# LB_BIT_i34_RANDOM-v03_3_4_-OHW.net
KiCad netlist of a schematic drawn in EAGLE
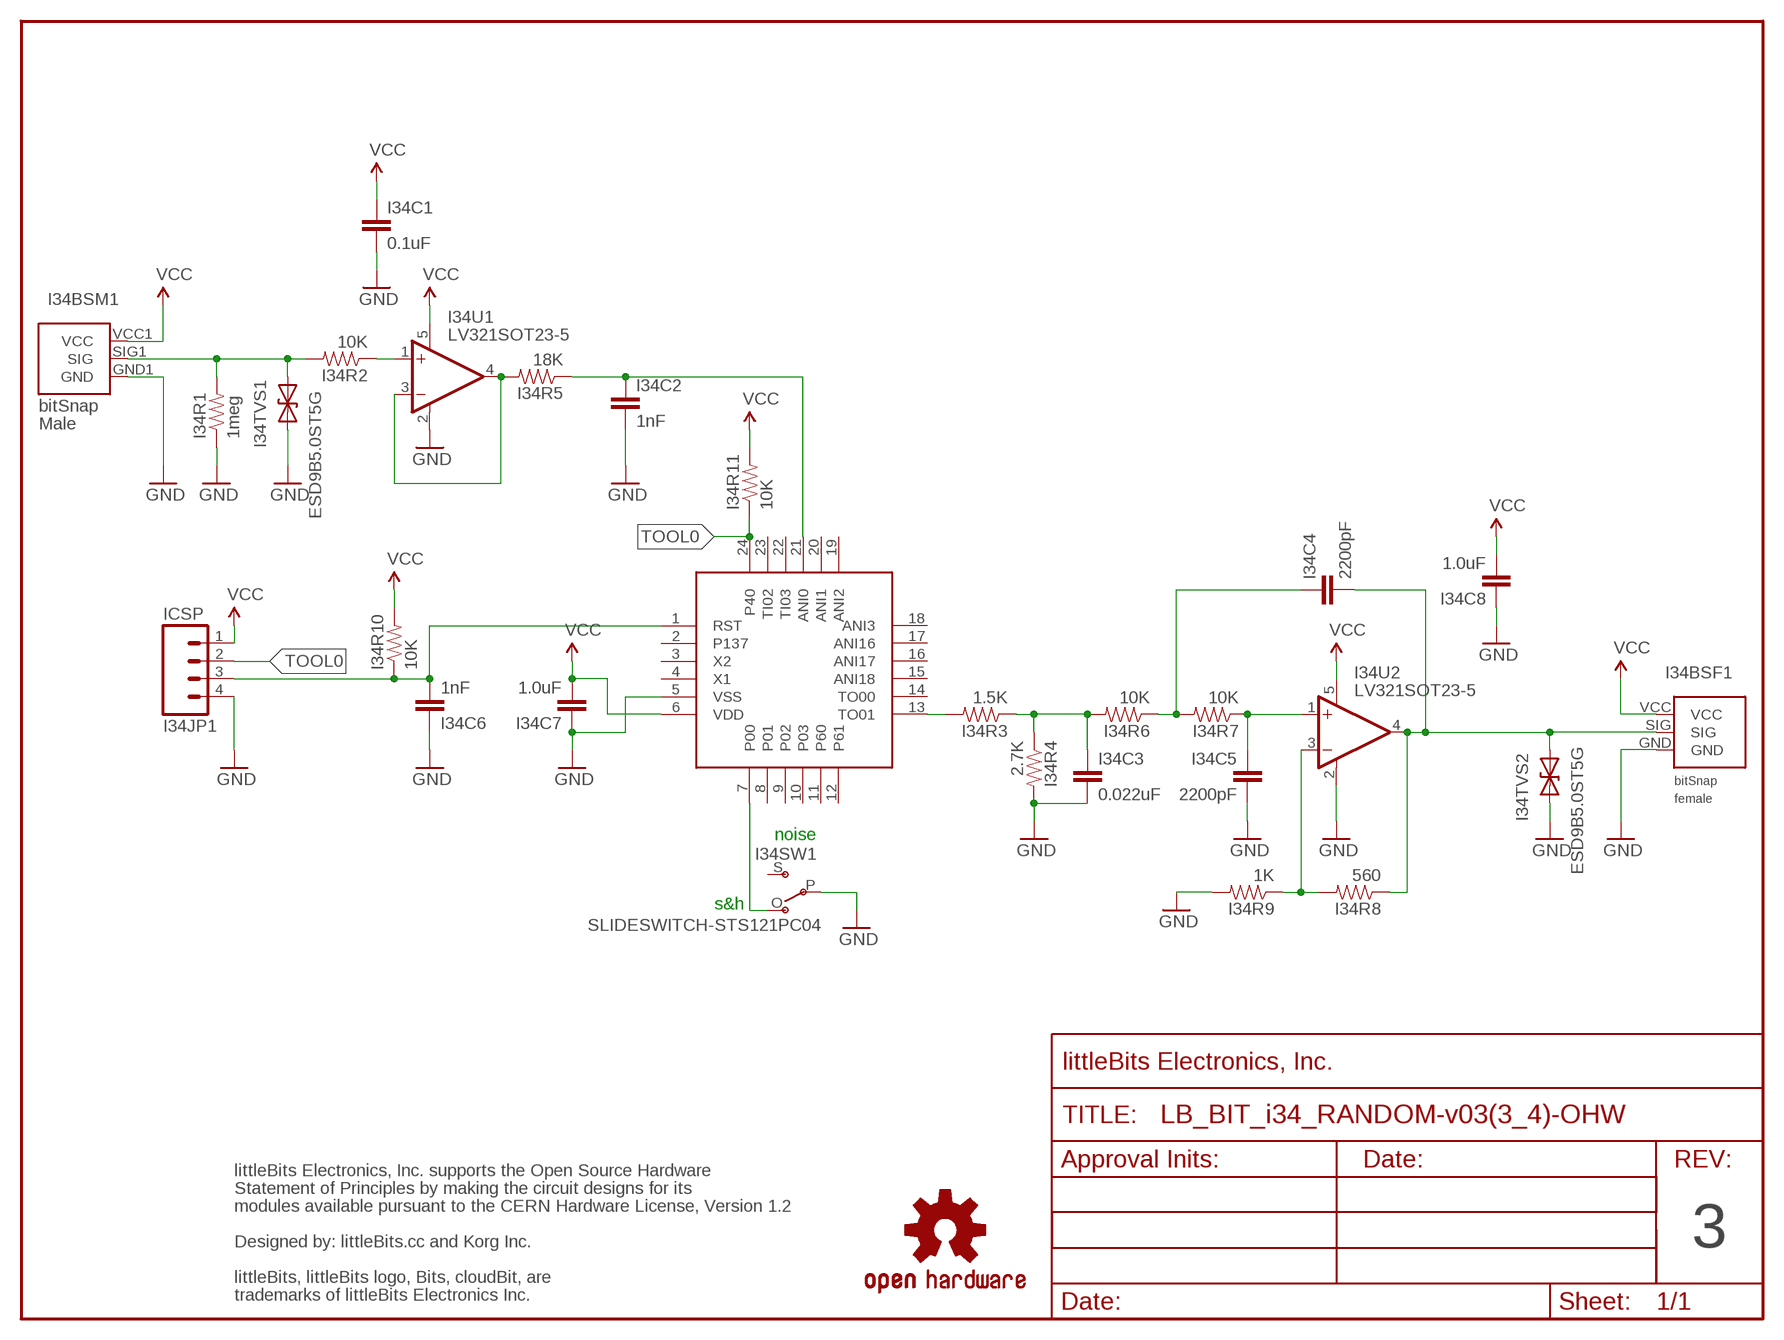
[diagram p0: schematic, sheet 1]

(export (version "E")
  (design (tool "Eeschema 10.0.6"))
  (components
    (comp (ref "I34BSF1")
      (value "BITSNAP_V03_FEMALE")
      (footprint "eagle-import:BITSNAP_V03_FEMALE")
      (libsource (lib "eagle-import") (part "BITSNAP_V03_FEMALE"))
    )
    (comp (ref "I34BSM1")
      (value "BITSNAP_V03_MALE")
      (footprint "eagle-import:BITSNAP_V03_MALE")
      (libsource (lib "eagle-import") (part "BITSNAP_V03_MALE"))
    )
    (comp (ref "I34C1")
      (value "0.1uF")
      (footprint "eagle-import:CAP-0603")
      (libsource (lib "eagle-import") (part "CAPCAP-0603"))
    )
    (comp (ref "I34C2")
      (value "1nF")
      (footprint "eagle-import:CAP-0603")
      (libsource (lib "eagle-import") (part "CAPCAP-0603"))
    )
    (comp (ref "I34C3")
      (value "0.022uF")
      (footprint "eagle-import:CAP-0603")
      (libsource (lib "eagle-import") (part "CAPCAP-0603"))
    )
    (comp (ref "I34C4")
      (value "2200pF")
      (footprint "eagle-import:CAP-0603")
      (libsource (lib "eagle-import") (part "CAPCAP-0603"))
    )
    (comp (ref "I34C5")
      (value "2200pF")
      (footprint "eagle-import:CAP-0603")
      (libsource (lib "eagle-import") (part "CAPCAP-0603"))
    )
    (comp (ref "I34C6")
      (value "1nF")
      (footprint "eagle-import:CAP-0603")
      (libsource (lib "eagle-import") (part "CAPCAP-0603"))
    )
    (comp (ref "I34C7")
      (value "1.0uF")
      (footprint "eagle-import:CAP-0603")
      (libsource (lib "eagle-import") (part "CAPCAP-0603"))
    )
    (comp (ref "I34C8")
      (value "1.0uF")
      (footprint "eagle-import:CAP-0603")
      (libsource (lib "eagle-import") (part "CAPCAP-0603"))
    )
    (comp (ref "I34JP1")
      (value "ICSP")
      (footprint "eagle-import:SIP4-SM-0.1IN-NOS.S.")
      (libsource (lib "eagle-import") (part "HDR-4SM_SML"))
    )
    (comp (ref "I34R1")
      (value "1meg")
      (footprint "eagle-import:RES-0603")
      (libsource (lib "eagle-import") (part "RESISTOR0603"))
    )
    (comp (ref "I34R2")
      (value "10K")
      (footprint "eagle-import:RES-0603")
      (libsource (lib "eagle-import") (part "RESISTOR0603"))
    )
    (comp (ref "I34R3")
      (value "1.5K")
      (footprint "eagle-import:RES-0603")
      (libsource (lib "eagle-import") (part "RESISTOR0603"))
    )
    (comp (ref "I34R4")
      (value "2.7K")
      (footprint "eagle-import:RES-0603")
      (libsource (lib "eagle-import") (part "RESISTOR0603"))
    )
    (comp (ref "I34R5")
      (value "18K")
      (footprint "eagle-import:RES-0603")
      (libsource (lib "eagle-import") (part "RESISTOR0603"))
    )
    (comp (ref "I34R6")
      (value "10K")
      (footprint "eagle-import:RES-0603")
      (libsource (lib "eagle-import") (part "RESISTOR0603"))
    )
    (comp (ref "I34R7")
      (value "10K")
      (footprint "eagle-import:RES-0603")
      (libsource (lib "eagle-import") (part "RESISTOR0603"))
    )
    (comp (ref "I34R8")
      (value "560")
      (footprint "eagle-import:RES-0603")
      (libsource (lib "eagle-import") (part "RESISTOR0603"))
    )
    (comp (ref "I34R9")
      (value "1K")
      (footprint "eagle-import:RES-0603")
      (libsource (lib "eagle-import") (part "RESISTOR0603"))
    )
    (comp (ref "I34R10")
      (value "10K")
      (footprint "eagle-import:RES-0603")
      (libsource (lib "eagle-import") (part "RESISTOR0603"))
    )
    (comp (ref "I34R11")
      (value "10K")
      (footprint "eagle-import:RES-0603")
      (libsource (lib "eagle-import") (part "RESISTOR0603"))
    )
    (comp (ref "I34SW1")
      (value "SLIDESWITCH-STS121PC04")
      (footprint "eagle-import:SLIDESWITCH-STS121PC04")
      (libsource (lib "eagle-import") (part "SLIDESWITCH-STS121PC04"))
    )
    (comp (ref "I34TVS1")
      (value "ESD9B5.0ST5G")
      (footprint "eagle-import:SOD-923")
      (libsource (lib "eagle-import") (part "DIODE-TVSSOD-923"))
    )
    (comp (ref "I34TVS2")
      (value "ESD9B5.0ST5G")
      (footprint "eagle-import:SOD-923")
      (libsource (lib "eagle-import") (part "DIODE-TVSSOD-923"))
    )
    (comp (ref "I34U1")
      (value "LV321SOT23-5")
      (footprint "eagle-import:SOT23-5")
      (libsource (lib "eagle-import") (part "LV321SOT23-5"))
    )
    (comp (ref "I34U2")
      (value "LV321SOT23-5")
      (footprint "eagle-import:SOT23-5")
      (libsource (lib "eagle-import") (part "LV321SOT23-5"))
    )
    (comp (ref "I34U3")
      (value "R5F10278QFN-24")
      (footprint "eagle-import:QFN-24(4MM)")
      (libsource (lib "eagle-import") (part "R5F10278QFN-24"))
    )
    (comp (ref "U$1")
      (value "FRAME-LETTER-OHWOHW")
      (footprint "eagle-import:FABDWG01-OHW")
      (libsource (lib "eagle-import") (part "FRAME-LETTER-OHWOHW"))
    )
    (comp (ref "U$2")
      (value "OSHWCREDIT-KORG")
      (footprint "eagle-import:OSHWCREDIT-KORG")
      (libsource (lib "eagle-import") (part "OSHWCREDIT-KORG"))
    )
    (comp (ref "U$3")
      (value "OSHW-LOGOL")
      (footprint "eagle-import:OSHW-LOGO-L")
      (libsource (lib "eagle-import") (part "OSHW-LOGOL"))
    )
  )
  (nets
    (net (code "1") (name "GND") (class "Default")
      (node (ref "I34BSF1") (pin "GND") (pinfunction "GND_GND") (pintype "bidirectional"))
      (node (ref "I34BSM1") (pin "GND1") (pinfunction "GND_GND1") (pintype "bidirectional"))
      (node (ref "I34C1") (pin "2") (pinfunction "2_2") (pintype "passive"))
      (node (ref "I34C2") (pin "2") (pinfunction "2_2") (pintype "passive"))
      (node (ref "I34C3") (pin "2") (pinfunction "2_2") (pintype "passive"))
      (node (ref "I34C5") (pin "2") (pinfunction "2_2") (pintype "passive"))
      (node (ref "I34C6") (pin "1") (pinfunction "1_1") (pintype "passive"))
      (node (ref "I34C7") (pin "1") (pinfunction "1_1") (pintype "passive"))
      (node (ref "I34C8") (pin "1") (pinfunction "1_1") (pintype "passive"))
      (node (ref "I34JP1") (pin "4") (pinfunction "4_4") (pintype "passive"))
      (node (ref "I34R1") (pin "1") (pinfunction "1_1") (pintype "passive"))
      (node (ref "I34R4") (pin "2") (pinfunction "2_2") (pintype "passive"))
      (node (ref "I34R9") (pin "2") (pinfunction "2_2") (pintype "passive"))
      (node (ref "I34SW1") (pin "P") (pinfunction "P_P") (pintype "passive"))
      (node (ref "I34TVS1") (pin "1") (pinfunction "A_1") (pintype "passive"))
      (node (ref "I34TVS2") (pin "1") (pinfunction "A_1") (pintype "passive"))
      (node (ref "I34U1") (pin "2") (pinfunction "V-_2") (pintype "power_in"))
      (node (ref "I34U2") (pin "2") (pinfunction "V-_2") (pintype "power_in"))
      (node (ref "I34U3") (pin "5") (pinfunction "VSS_5") (pintype "bidirectional"))
    )
    (net (code "2") (name "Net-(I34BSM1-SIG)") (class "Default")
      (node (ref "I34BSM1") (pin "SIG1") (pinfunction "SIG_SIG1") (pintype "bidirectional"))
      (node (ref "I34R1") (pin "2") (pinfunction "2_2") (pintype "passive"))
      (node (ref "I34R2") (pin "2") (pinfunction "2_2") (pintype "passive"))
      (node (ref "I34TVS1") (pin "2") (pinfunction "C_2") (pintype "passive"))
    )
    (net (code "3") (name "Net-(I34C3-Pad1)") (class "Default")
      (node (ref "I34C3") (pin "1") (pinfunction "1_1") (pintype "passive"))
      (node (ref "I34R3") (pin "1") (pinfunction "1_1") (pintype "passive"))
      (node (ref "I34R4") (pin "1") (pinfunction "1_1") (pintype "passive"))
      (node (ref "I34R6") (pin "2") (pinfunction "2_2") (pintype "passive"))
    )
    (net (code "4") (name "Net-(I34C4-Pad1)") (class "Default")
      (node (ref "I34C4") (pin "1") (pinfunction "1_1") (pintype "passive"))
      (node (ref "I34R6") (pin "1") (pinfunction "1_1") (pintype "passive"))
      (node (ref "I34R7") (pin "2") (pinfunction "2_2") (pintype "passive"))
    )
    (net (code "5") (name "Net-(I34TVS2-C)") (class "Default")
      (node (ref "I34BSF1") (pin "SIG") (pinfunction "SIG_SIG") (pintype "bidirectional"))
      (node (ref "I34C4") (pin "2") (pinfunction "2_2") (pintype "passive"))
      (node (ref "I34R8") (pin "1") (pinfunction "1_1") (pintype "passive"))
      (node (ref "I34TVS2") (pin "2") (pinfunction "C_2") (pintype "passive"))
      (node (ref "I34U2") (pin "4") (pinfunction "OUT_4") (pintype "output"))
    )
    (net (code "6") (name "Net-(I34U1-+IN)") (class "Default")
      (node (ref "I34R2") (pin "1") (pinfunction "1_1") (pintype "passive"))
      (node (ref "I34U1") (pin "1") (pinfunction "+IN_1") (pintype "input"))
    )
    (net (code "7") (name "Net-(I34U1--IN)") (class "Default")
      (node (ref "I34R5") (pin "2") (pinfunction "2_2") (pintype "passive"))
      (node (ref "I34U1") (pin "3") (pinfunction "-IN_3") (pintype "input"))
      (node (ref "I34U1") (pin "4") (pinfunction "OUT_4") (pintype "output"))
    )
    (net (code "8") (name "Net-(I34U2-+IN)") (class "Default")
      (node (ref "I34C5") (pin "1") (pinfunction "1_1") (pintype "passive"))
      (node (ref "I34R7") (pin "1") (pinfunction "1_1") (pintype "passive"))
      (node (ref "I34U2") (pin "1") (pinfunction "+IN_1") (pintype "input"))
    )
    (net (code "9") (name "Net-(I34U2--IN)") (class "Default")
      (node (ref "I34R8") (pin "2") (pinfunction "2_2") (pintype "passive"))
      (node (ref "I34R9") (pin "1") (pinfunction "1_1") (pintype "passive"))
      (node (ref "I34U2") (pin "3") (pinfunction "-IN_3") (pintype "input"))
    )
    (net (code "10") (name "Net-(I34U3-ANI0)") (class "Default")
      (node (ref "I34C2") (pin "1") (pinfunction "1_1") (pintype "passive"))
      (node (ref "I34R5") (pin "1") (pinfunction "1_1") (pintype "passive"))
      (node (ref "I34U3") (pin "21") (pinfunction "ANI0_21") (pintype "bidirectional"))
    )
    (net (code "11") (name "Net-(I34U3-P00)") (class "Default")
      (node (ref "I34SW1") (pin "O") (pinfunction "O_O") (pintype "passive"))
      (node (ref "I34U3") (pin "7") (pinfunction "P00_7") (pintype "bidirectional"))
    )
    (net (code "12") (name "Net-(I34U3-RST)") (class "Default")
      (node (ref "I34C6") (pin "2") (pinfunction "2_2") (pintype "passive"))
      (node (ref "I34JP1") (pin "3") (pinfunction "3_3") (pintype "passive"))
      (node (ref "I34R10") (pin "1") (pinfunction "1_1") (pintype "passive"))
      (node (ref "I34U3") (pin "1") (pinfunction "RST_1") (pintype "bidirectional"))
    )
    (net (code "13") (name "Net-(I34U3-TO01)") (class "Default")
      (node (ref "I34R3") (pin "2") (pinfunction "2_2") (pintype "passive"))
      (node (ref "I34U3") (pin "13") (pinfunction "TO01_13") (pintype "bidirectional"))
    )
    (net (code "14") (name "TOOL0") (class "Default")
      (node (ref "I34JP1") (pin "2") (pinfunction "2_2") (pintype "passive"))
      (node (ref "I34R11") (pin "1") (pinfunction "1_1") (pintype "passive"))
      (node (ref "I34U3") (pin "24") (pinfunction "P40_24") (pintype "bidirectional"))
    )
    (net (code "15") (name "VCC") (class "Default")
      (node (ref "I34BSF1") (pin "VCC") (pinfunction "VCC_VCC") (pintype "bidirectional"))
      (node (ref "I34BSM1") (pin "VCC1") (pinfunction "VCC_VCC1") (pintype "bidirectional"))
      (node (ref "I34C1") (pin "1") (pinfunction "1_1") (pintype "passive"))
      (node (ref "I34C7") (pin "2") (pinfunction "2_2") (pintype "passive"))
      (node (ref "I34C8") (pin "2") (pinfunction "2_2") (pintype "passive"))
      (node (ref "I34JP1") (pin "1") (pinfunction "1_1") (pintype "passive"))
      (node (ref "I34R10") (pin "2") (pinfunction "2_2") (pintype "passive"))
      (node (ref "I34R11") (pin "2") (pinfunction "2_2") (pintype "passive"))
      (node (ref "I34U1") (pin "5") (pinfunction "V+_5") (pintype "power_in"))
      (node (ref "I34U2") (pin "5") (pinfunction "V+_5") (pintype "power_in"))
      (node (ref "I34U3") (pin "6") (pinfunction "VDD_6") (pintype "bidirectional"))
    )
    (net (code "16") (name "unconnected-(I34SW1-PadS)") (class "Default")
      (node (ref "I34SW1") (pin "S") (pinfunction "S_S") (pintype "passive"))
    )
    (net (code "17") (name "unconnected-(I34U3-ANI1-Pad20)") (class "Default")
      (node (ref "I34U3") (pin "20") (pinfunction "ANI1_20") (pintype "bidirectional"))
    )
    (net (code "18") (name "unconnected-(I34U3-ANI2-Pad19)") (class "Default")
      (node (ref "I34U3") (pin "19") (pinfunction "ANI2_19") (pintype "bidirectional"))
    )
    (net (code "19") (name "unconnected-(I34U3-ANI3-Pad18)") (class "Default")
      (node (ref "I34U3") (pin "18") (pinfunction "ANI3_18") (pintype "bidirectional"))
    )
    (net (code "20") (name "unconnected-(I34U3-ANI16-Pad17)") (class "Default")
      (node (ref "I34U3") (pin "17") (pinfunction "ANI16_17") (pintype "bidirectional"))
    )
    (net (code "21") (name "unconnected-(I34U3-ANI17-Pad16)") (class "Default")
      (node (ref "I34U3") (pin "16") (pinfunction "ANI17_16") (pintype "bidirectional"))
    )
    (net (code "22") (name "unconnected-(I34U3-ANI18-Pad15)") (class "Default")
      (node (ref "I34U3") (pin "15") (pinfunction "ANI18_15") (pintype "bidirectional"))
    )
    (net (code "23") (name "unconnected-(I34U3-P01-Pad8)") (class "Default")
      (node (ref "I34U3") (pin "8") (pinfunction "P01_8") (pintype "bidirectional"))
    )
    (net (code "24") (name "unconnected-(I34U3-P02-Pad9)") (class "Default")
      (node (ref "I34U3") (pin "9") (pinfunction "P02_9") (pintype "bidirectional"))
    )
    (net (code "25") (name "unconnected-(I34U3-P03-Pad10)") (class "Default")
      (node (ref "I34U3") (pin "10") (pinfunction "P03_10") (pintype "bidirectional"))
    )
    (net (code "26") (name "unconnected-(I34U3-P60-Pad11)") (class "Default")
      (node (ref "I34U3") (pin "11") (pinfunction "P60_11") (pintype "bidirectional"))
    )
    (net (code "27") (name "unconnected-(I34U3-P61-Pad12)") (class "Default")
      (node (ref "I34U3") (pin "12") (pinfunction "P61_12") (pintype "bidirectional"))
    )
    (net (code "28") (name "unconnected-(I34U3-P137-Pad2)") (class "Default")
      (node (ref "I34U3") (pin "2") (pinfunction "P137_2") (pintype "bidirectional"))
    )
    (net (code "29") (name "unconnected-(I34U3-TI02-Pad23)") (class "Default")
      (node (ref "I34U3") (pin "23") (pinfunction "TI02_23") (pintype "bidirectional"))
    )
    (net (code "30") (name "unconnected-(I34U3-TI03-Pad22)") (class "Default")
      (node (ref "I34U3") (pin "22") (pinfunction "TI03_22") (pintype "bidirectional"))
    )
    (net (code "31") (name "unconnected-(I34U3-TO00-Pad14)") (class "Default")
      (node (ref "I34U3") (pin "14") (pinfunction "TO00_14") (pintype "bidirectional"))
    )
    (net (code "32") (name "unconnected-(I34U3-X1-Pad4)") (class "Default")
      (node (ref "I34U3") (pin "4") (pinfunction "X1_4") (pintype "bidirectional"))
    )
    (net (code "33") (name "unconnected-(I34U3-X2-Pad3)") (class "Default")
      (node (ref "I34U3") (pin "3") (pinfunction "X2_3") (pintype "bidirectional"))
    )
  )
)
